# OPT3001.net
KiCad netlist of a schematic drawn in EAGLE
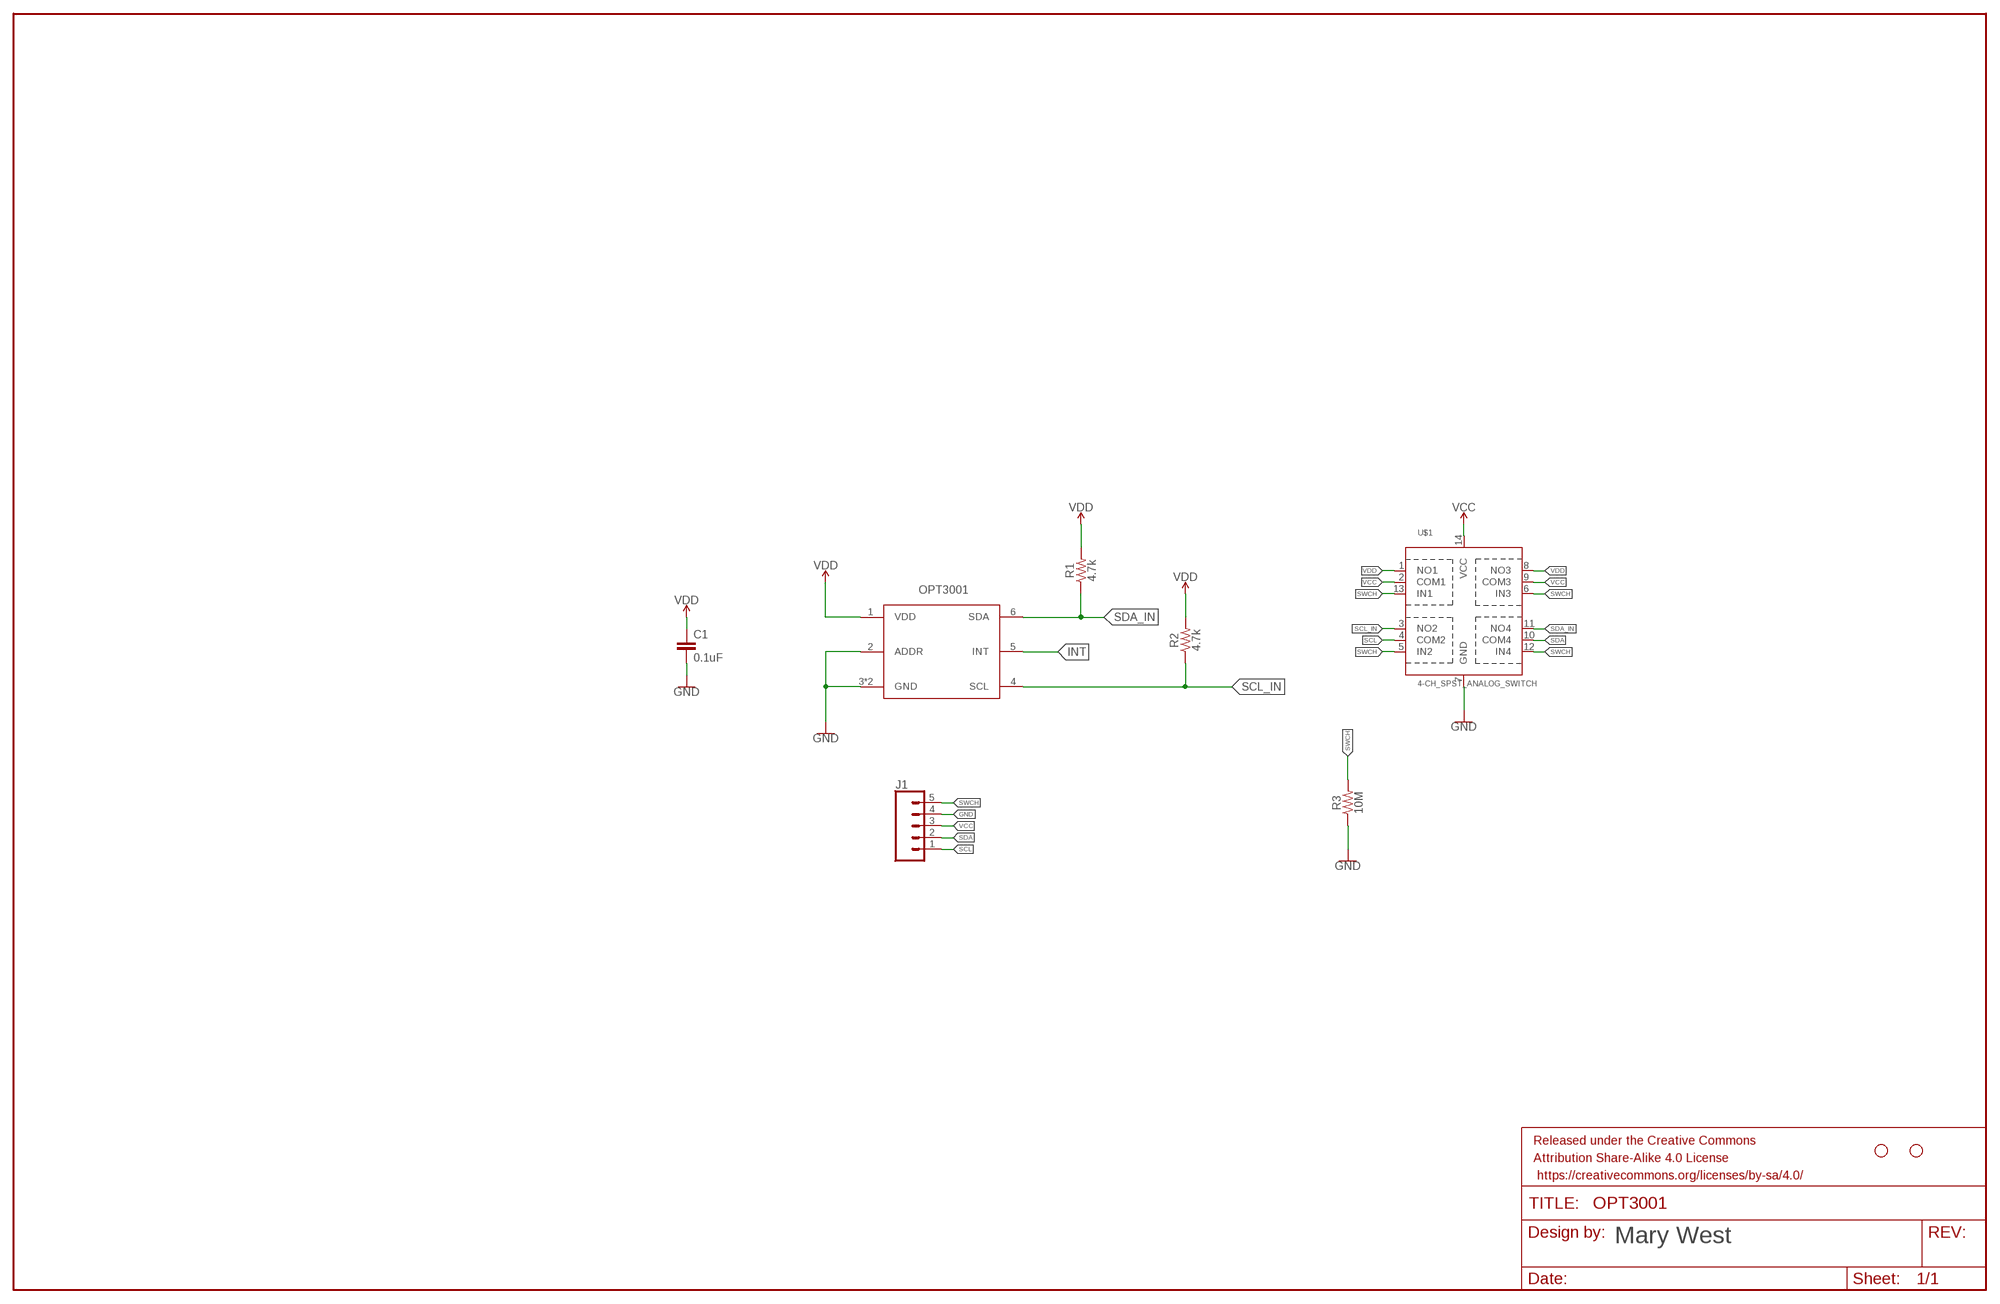
[diagram p0: schematic, sheet 1]

(export (version "E")
  (design (tool "Eeschema 10.0.6"))
  (components
    (comp (ref "C1")
      (value "0.1uF")
      (footprint "eagle-import:0603")
      (libsource (lib "eagle-import") (part "0.1UF-0603-25V-(+80/-20%)"))
    )
    (comp (ref "FRAME1")
      (value "FRAME-LEDGER")
      (footprint "eagle-import:CREATIVE_COMMONS")
      (libsource (lib "eagle-import") (part "FRAME-LEDGER"))
    )
    (comp (ref "H1")
      (value "STAND-OFF")
      (footprint "eagle-import:STAND-OFF")
      (libsource (lib "eagle-import") (part "STAND-OFF"))
    )
    (comp (ref "H2")
      (value "STAND-OFF")
      (footprint "eagle-import:STAND-OFF")
      (libsource (lib "eagle-import") (part "STAND-OFF"))
    )
    (comp (ref "J1")
      (value "CONN_05")
      (footprint "eagle-import:1X05")
      (libsource (lib "eagle-import") (part "CONN_05"))
    )
    (comp (ref "OPT3001")
      (value "OPT3001DNPT")
      (footprint "eagle-import:6PIN_USON")
      (libsource (lib "eagle-import") (part "OPT3001DNPT"))
    )
    (comp (ref "R1")
      (value "4.7k")
      (footprint "eagle-import:0603")
      (libsource (lib "eagle-import") (part "4.7KOHM-0603-1/10W-1%"))
    )
    (comp (ref "R2")
      (value "4.7k")
      (footprint "eagle-import:0603")
      (libsource (lib "eagle-import") (part "4.7KOHM-0603-1/10W-1%"))
    )
    (comp (ref "R3")
      (value "10M")
      (footprint "eagle-import:0603")
      (libsource (lib "eagle-import") (part "10MOHM-0603-1/10W-5%"))
    )
    (comp (ref "U$1")
      (value "4-CH_SPST_ANALOG_SWITCH")
      (footprint "eagle-import:TSSOP14")
      (libsource (lib "eagle-import") (part "4-CH_SPST_ANALOG_SWITCH"))
    )
  )
  (nets
    (net (code "1") (name "GND") (class "Default")
      (node (ref "C1") (pin "2") (pinfunction "2_2") (pintype "passive"))
      (node (ref "J1") (pin "4") (pinfunction "4_4") (pintype "passive"))
      (node (ref "OPT3001") (pin "2") (pinfunction "ADDR_2") (pintype "bidirectional"))
      (node (ref "OPT3001") (pin "3") (pinfunction "GND_3") (pintype "bidirectional"))
      (node (ref "OPT3001") (pin "GND") (pinfunction "GND_GND") (pintype "bidirectional"))
      (node (ref "R3") (pin "1") (pinfunction "1_1") (pintype "passive"))
      (node (ref "U$1") (pin "7") (pinfunction "GND_7") (pintype "bidirectional"))
    )
    (net (code "2") (name "INT") (class "Default")
      (node (ref "OPT3001") (pin "5") (pinfunction "INT_5") (pintype "bidirectional"))
    )
    (net (code "3") (name "SCL") (class "Default")
      (node (ref "J1") (pin "1") (pinfunction "1_1") (pintype "passive"))
      (node (ref "U$1") (pin "4") (pinfunction "COM2_4") (pintype "bidirectional"))
    )
    (net (code "4") (name "SCL_IN") (class "Default")
      (node (ref "OPT3001") (pin "4") (pinfunction "SCL_4") (pintype "bidirectional"))
      (node (ref "R2") (pin "1") (pinfunction "1_1") (pintype "passive"))
      (node (ref "U$1") (pin "3") (pinfunction "NO2_3") (pintype "bidirectional"))
    )
    (net (code "5") (name "SDA") (class "Default")
      (node (ref "J1") (pin "2") (pinfunction "2_2") (pintype "passive"))
      (node (ref "U$1") (pin "10") (pinfunction "COM4_10") (pintype "bidirectional"))
    )
    (net (code "6") (name "SDA_IN") (class "Default")
      (node (ref "OPT3001") (pin "6") (pinfunction "SDA_6") (pintype "bidirectional"))
      (node (ref "R1") (pin "1") (pinfunction "1_1") (pintype "passive"))
      (node (ref "U$1") (pin "11") (pinfunction "NO4_11") (pintype "bidirectional"))
    )
    (net (code "7") (name "SWCH") (class "Default")
      (node (ref "J1") (pin "5") (pinfunction "5_5") (pintype "passive"))
      (node (ref "R3") (pin "2") (pinfunction "2_2") (pintype "passive"))
      (node (ref "U$1") (pin "12") (pinfunction "IN4_12") (pintype "bidirectional"))
      (node (ref "U$1") (pin "13") (pinfunction "IN1_13") (pintype "bidirectional"))
      (node (ref "U$1") (pin "5") (pinfunction "IN2_5") (pintype "bidirectional"))
      (node (ref "U$1") (pin "6") (pinfunction "IN3_6") (pintype "bidirectional"))
    )
    (net (code "8") (name "VCC") (class "Default")
      (node (ref "J1") (pin "3") (pinfunction "3_3") (pintype "passive"))
      (node (ref "U$1") (pin "14") (pinfunction "VCC_14") (pintype "bidirectional"))
      (node (ref "U$1") (pin "2") (pinfunction "COM1_2") (pintype "bidirectional"))
      (node (ref "U$1") (pin "9") (pinfunction "COM3_9") (pintype "bidirectional"))
    )
    (net (code "9") (name "VDD") (class "Default")
      (node (ref "C1") (pin "1") (pinfunction "1_1") (pintype "passive"))
      (node (ref "OPT3001") (pin "1") (pinfunction "VDD_1") (pintype "bidirectional"))
      (node (ref "R1") (pin "2") (pinfunction "2_2") (pintype "passive"))
      (node (ref "R2") (pin "2") (pinfunction "2_2") (pintype "passive"))
      (node (ref "U$1") (pin "1") (pinfunction "NO1_1") (pintype "bidirectional"))
      (node (ref "U$1") (pin "8") (pinfunction "NO3_8") (pintype "bidirectional"))
    )
  )
)
